# Sheet1.net
KiCad netlist of a schematic drawn in Altium Designer
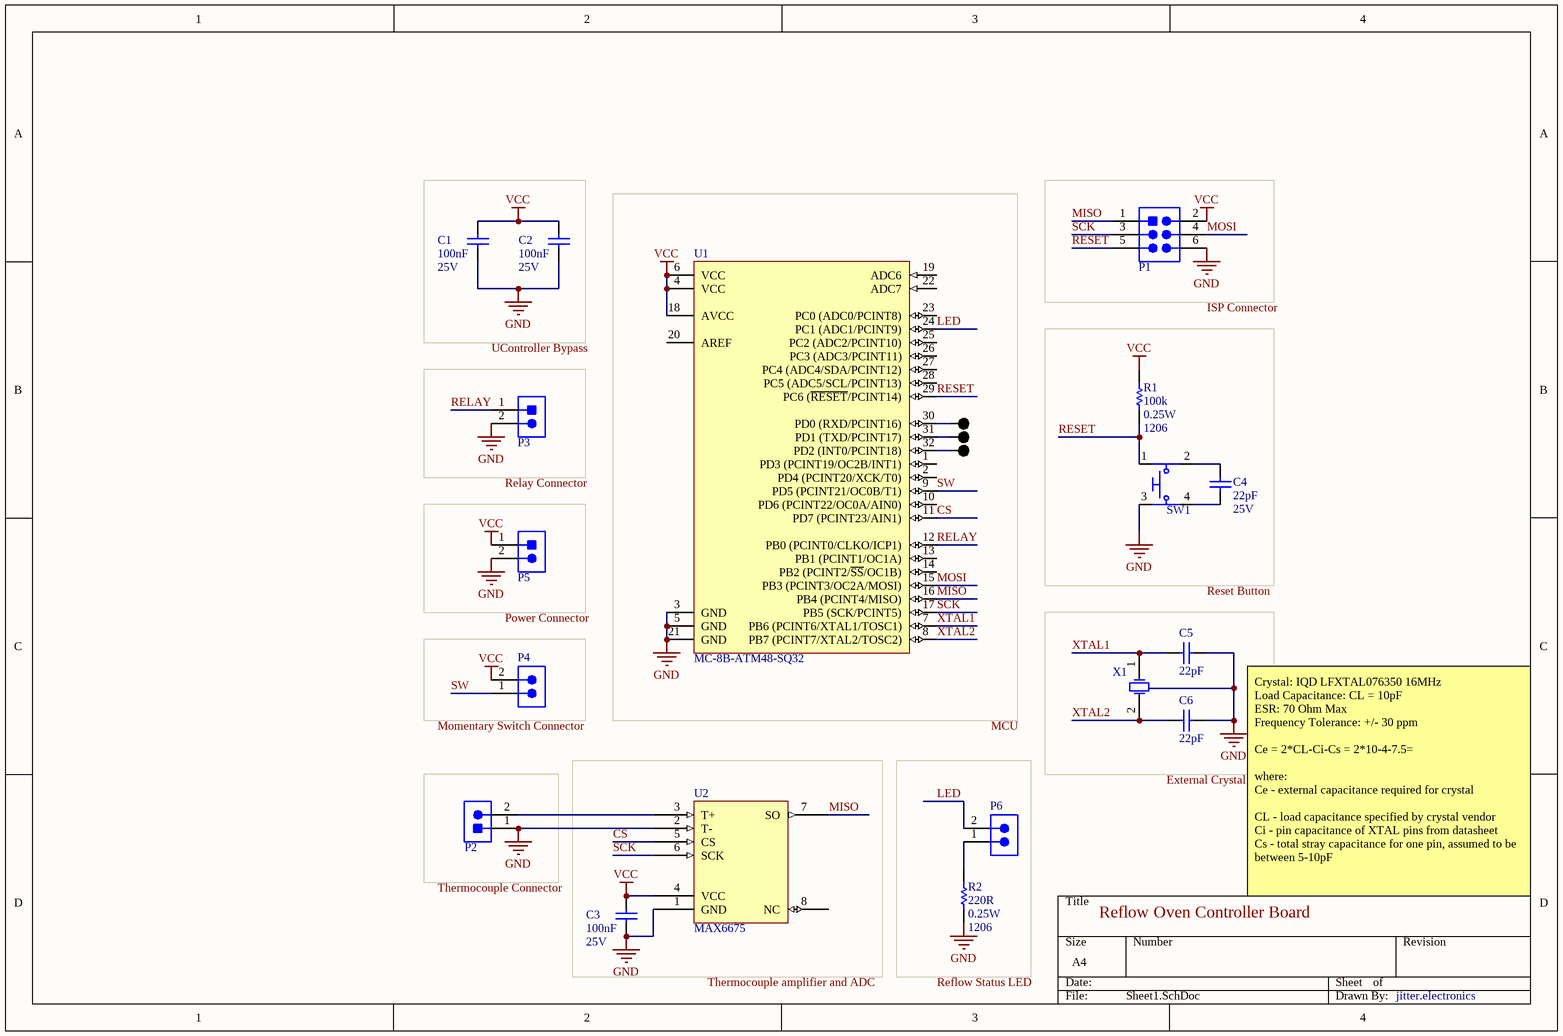
[diagram p0: Sheet1.SchDoc]

(export (version "E")
  (design (tool "Eeschema 10.0.6"))
  (components
    (comp (ref "1")
      (value "1MM_HOLE")
      (footprint "1MM_HOLE")
      (description "1mm hole and pad for breakouts")
      (libsource (lib "PCB_mechanical") (part "1MM_HOLE"))
    )
    (comp (ref "2")
      (value "1MM_HOLE")
      (footprint "1MM_HOLE")
      (description "1mm hole and pad for breakouts")
      (libsource (lib "PCB_mechanical") (part "1MM_HOLE"))
    )
    (comp (ref "3")
      (value "1MM_HOLE")
      (footprint "1MM_HOLE")
      (description "1mm hole and pad for breakouts")
      (libsource (lib "PCB_mechanical") (part "1MM_HOLE"))
    )
    (comp (ref "C1")
      (value "100nF")
      (footprint "CAPC0805(2012)75_N")
      (fields (field (name "VOLTAGE") "25V") (field (name "Comment") "CAP"))
      (libsource (lib "capacitors") (part "CAP"))
    )
    (comp (ref "C2")
      (value "100nF")
      (footprint "CAPC0805(2012)75_N")
      (fields (field (name "VOLTAGE") "25V") (field (name "Comment") "CAP"))
      (libsource (lib "capacitors") (part "CAP"))
    )
    (comp (ref "C3")
      (value "100nF")
      (footprint "CAPC0805(2012)75_N")
      (fields (field (name "VOLTAGE") "25V") (field (name "Comment") "CAP"))
      (libsource (lib "capacitors") (part "CAP"))
    )
    (comp (ref "C4")
      (value "22pF")
      (footprint "CAPC0805(2012)75_N")
      (fields (field (name "VOLTAGE") "25V") (field (name "Comment") "CAP"))
      (libsource (lib "capacitors") (part "CAP"))
    )
    (comp (ref "C5")
      (value "22pF")
      (footprint "CAPC0805(2012)75_N")
      (fields (field (name "VOLTAGE") "25V") (field (name "Comment") "CAP"))
      (libsource (lib "capacitors") (part "CAP"))
    )
    (comp (ref "C6")
      (value "22pF")
      (footprint "CAPC0805(2012)75_N")
      (fields (field (name "VOLTAGE") "25V") (field (name "Comment") "CAP"))
      (libsource (lib "capacitors") (part "CAP"))
    )
    (comp (ref "P1")
      (value "2X3-2.54mm-HEADER")
      (footprint "PCE-BH2542-10-SPGRH-3.0")
      (description "2x3 2.54mm Header")
      (libsource (lib "connectors") (part "2X3-2.54mm-HEADER"))
    )
    (comp (ref "P2")
      (value "CTBP5000/2")
      (footprint "Camden Boss CTBP5000/2")
      (description "Socket, Screw Terminal Block, 2-Leads, Pitch 5mm, 90 Degree Angle, Through-Hole")
      (libsource (lib "") (part "CTBP5000/2_1"))
    )
    (comp (ref "P3")
      (value "CTBP5000/2")
      (footprint "Camden Boss CTBP5000/2")
      (description "Socket, Screw Terminal Block, 2-Leads, Pitch 5mm, 90 Degree Angle, Through-Hole")
      (libsource (lib "connectors") (part "CTBP5000/2"))
    )
    (comp (ref "P4")
      (value "B2B-XH-A HEADER")
      (footprint "B2B-XH-A")
      (description "Wire-To-Board Connector, Vertical, 2.5 mm, 2 Contacts, Header, XH Series, Through Hole, 1 Rows")
      (libsource (lib "connectors") (part "B2B-XH-A HEADER"))
    )
    (comp (ref "P5")
      (value "CTBP5000/2")
      (footprint "Camden Boss CTBP5000/2")
      (description "Socket, Screw Terminal Block, 2-Leads, Pitch 5mm, 90 Degree Angle, Through-Hole")
      (libsource (lib "connectors") (part "CTBP5000/2"))
    )
    (comp (ref "P6")
      (value "B2B-XH-A HEADER")
      (footprint "B2B-XH-A")
      (description "Wire-To-Board Connector, Vertical, 2.5 mm, 2 Contacts, Header, XH Series, Through Hole, 1 Rows")
      (libsource (lib "connectors") (part "B2B-XH-A HEADER"))
    )
    (comp (ref "R1")
      (value "100k")
      (footprint "RESC1206(3216)_N")
      (fields (field (name "RATING") "0.25W") (field (name "FOOT") "1206") (field (name "Comment") "RES"))
      (libsource (lib "resistors") (part "RES"))
    )
    (comp (ref "R2")
      (value "220R")
      (footprint "RESC1206(3216)_N")
      (fields (field (name "RATING") "0.25W") (field (name "FOOT") "1206") (field (name "Comment") "RES"))
      (libsource (lib "resistors") (part "RES"))
    )
    (comp (ref "SW1")
      (value "SW-SPST-4_A")
      (footprint "sw_PB_SMD")
      (libsource (lib "switches") (part "SW-SPST-4_A"))
    )
    (comp (ref "U1")
      (value "MC-8B-ATM48-SQ32")
      (footprint "32A_L")
      (description "ATMEGA 328P")
      (libsource (lib "microcontrollers") (part "MC-8B-ATM48-SQ32"))
    )
    (comp (ref "U2")
      (value "MAX6675")
      (footprint "D0008A_N")
      (libsource (lib "Amplifiers") (part "MAX 6675"))
    )
    (comp (ref "X1")
      (value "LFXTAL076350")
      (footprint "LFXTAL076350")
      (description "16MHz SMD crystal")
      (libsource (lib "Crystal") (part "LFXTAL076350"))
    )
  )
  (nets
    (net (code "1") (name "/CS") (class "Default")
      (node (ref "U1") (pin "11") (pinfunction "PD7_(PCINT23/AIN1)_11") (pintype "bidirectional"))
      (node (ref "U2") (pin "5") (pinfunction "CS_5") (pintype "input"))
    )
    (net (code "2") (name "/LED") (class "Default")
      (node (ref "P6") (pin "2") (pinfunction "2_2") (pintype "passive"))
      (node (ref "U1") (pin "24") (pinfunction "PC1_(ADC1/PCINT9)_24") (pintype "bidirectional"))
    )
    (net (code "3") (name "/MISO") (class "Default")
      (node (ref "P1") (pin "1") (pinfunction "1_1") (pintype "passive"))
      (node (ref "U1") (pin "16") (pinfunction "PB4_(PCINT4/MISO)_16") (pintype "bidirectional"))
      (node (ref "U2") (pin "7") (pinfunction "SO_7") (pintype "output"))
    )
    (net (code "4") (name "/MOSI") (class "Default")
      (node (ref "P1") (pin "4") (pinfunction "4_4") (pintype "passive"))
      (node (ref "U1") (pin "15") (pinfunction "PB3_(PCINT3/OC2A/MOSI)_15") (pintype "bidirectional"))
    )
    (net (code "5") (name "/RELAY") (class "Default")
      (node (ref "P3") (pin "1") (pinfunction "1_1") (pintype "passive"))
      (node (ref "U1") (pin "12") (pinfunction "PB0_(PCINT0/CLKO/ICP1)_12") (pintype "bidirectional"))
    )
    (net (code "6") (name "/RESET") (class "Default")
      (node (ref "P1") (pin "5") (pinfunction "5_5") (pintype "passive"))
      (node (ref "R1") (pin "1") (pinfunction "1_1") (pintype "passive"))
      (node (ref "SW1") (pin "1") (pinfunction "1_1") (pintype "passive"))
      (node (ref "U1") (pin "29") (pinfunction "PC6_(~{RESET}/PCINT14)_29") (pintype "bidirectional"))
    )
    (net (code "7") (name "/SCK") (class "Default")
      (node (ref "P1") (pin "3") (pinfunction "3_3") (pintype "passive"))
      (node (ref "U1") (pin "17") (pinfunction "PB5_(SCK/PCINT5)_17") (pintype "bidirectional"))
      (node (ref "U2") (pin "6") (pinfunction "SCK_6") (pintype "input"))
    )
    (net (code "8") (name "/SW") (class "Default")
      (node (ref "P4") (pin "1") (pinfunction "1_1") (pintype "passive"))
      (node (ref "U1") (pin "9") (pinfunction "PD5_(PCINT21/OC0B/T1)_9") (pintype "bidirectional"))
    )
    (net (code "9") (name "/XTAL1") (class "Default")
      (node (ref "C5") (pin "2") (pinfunction "2_2") (pintype "passive"))
      (node (ref "U1") (pin "7") (pinfunction "PB6_(PCINT6/XTAL1/TOSC1)_7") (pintype "bidirectional"))
      (node (ref "X1") (pin "1") (pinfunction "X2_1") (pintype "passive"))
    )
    (net (code "10") (name "/XTAL2") (class "Default")
      (node (ref "C6") (pin "2") (pinfunction "2_2") (pintype "passive"))
      (node (ref "U1") (pin "8") (pinfunction "PB7_(PCINT7/XTAL2/TOSC2)_8") (pintype "bidirectional"))
      (node (ref "X1") (pin "2") (pinfunction "X1_2") (pintype "passive"))
    )
    (net (code "11") (name "GND") (class "Default")
      (node (ref "C1") (pin "1") (pinfunction "1_1") (pintype "passive"))
      (node (ref "C2") (pin "1") (pinfunction "1_1") (pintype "passive"))
      (node (ref "C3") (pin "1") (pinfunction "1_1") (pintype "passive"))
      (node (ref "C5") (pin "1") (pinfunction "1_1") (pintype "passive"))
      (node (ref "C6") (pin "1") (pinfunction "1_1") (pintype "passive"))
      (node (ref "P1") (pin "6") (pinfunction "6_6") (pintype "passive"))
      (node (ref "P2") (pin "1") (pinfunction "1_1") (pintype "passive"))
      (node (ref "P3") (pin "2") (pinfunction "2_2") (pintype "passive"))
      (node (ref "P5") (pin "2") (pinfunction "2_2") (pintype "passive"))
      (node (ref "R2") (pin "2") (pinfunction "2_2") (pintype "passive"))
      (node (ref "SW1") (pin "3") (pinfunction "3_3") (pintype "passive"))
      (node (ref "U1") (pin "21") (pinfunction "GND_21") (pintype "power_in"))
      (node (ref "U1") (pin "3") (pinfunction "GND_3") (pintype "power_in"))
      (node (ref "U1") (pin "5") (pinfunction "GND_5") (pintype "power_in"))
      (node (ref "U2") (pin "1") (pinfunction "GND_1") (pintype "power_in"))
      (node (ref "U2") (pin "2") (pinfunction "T-_2") (pintype "input"))
      (node (ref "X1") (pin "3") (pinfunction "GND_3") (pintype "power_in"))
    )
    (net (code "12") (name "Net-(C4-Pad1)") (class "Default")
      (node (ref "C4") (pin "1") (pinfunction "1_1") (pintype "passive"))
      (node (ref "SW1") (pin "2") (pinfunction "2_2") (pintype "passive"))
    )
    (net (code "13") (name "Net-(C4-Pad2)") (class "Default")
      (node (ref "C4") (pin "2") (pinfunction "2_2") (pintype "passive"))
      (node (ref "SW1") (pin "4") (pinfunction "4_4") (pintype "passive"))
    )
    (net (code "14") (name "Net-(P6-Pad1)") (class "Default")
      (node (ref "P6") (pin "1") (pinfunction "1_1") (pintype "passive"))
      (node (ref "R2") (pin "1") (pinfunction "1_1") (pintype "passive"))
    )
    (net (code "15") (name "Net-(U1-PD0_(RXD{slash}PCINT16))") (class "Default")
      (node (ref "1") (pin "1") (pinfunction "1_1") (pintype "passive"))
      (node (ref "U1") (pin "30") (pinfunction "PD0_(RXD/PCINT16)_30") (pintype "bidirectional"))
    )
    (net (code "16") (name "Net-(U1-PD1_(TXD{slash}PCINT17))") (class "Default")
      (node (ref "2") (pin "1") (pinfunction "1_1") (pintype "passive"))
      (node (ref "U1") (pin "31") (pinfunction "PD1_(TXD/PCINT17)_31") (pintype "bidirectional"))
    )
    (net (code "17") (name "Net-(U1-PD2_(INT0{slash}PCINT18))") (class "Default")
      (node (ref "3") (pin "1") (pinfunction "1_1") (pintype "passive"))
      (node (ref "U1") (pin "32") (pinfunction "PD2_(INT0/PCINT18)_32") (pintype "bidirectional"))
    )
    (net (code "18") (name "Net-(U2-T+)") (class "Default")
      (node (ref "P2") (pin "2") (pinfunction "2_2") (pintype "passive"))
      (node (ref "U2") (pin "3") (pinfunction "T+_3") (pintype "input"))
    )
    (net (code "19") (name "VCC") (class "Default")
      (node (ref "C1") (pin "2") (pinfunction "2_2") (pintype "passive"))
      (node (ref "C2") (pin "2") (pinfunction "2_2") (pintype "passive"))
      (node (ref "C3") (pin "2") (pinfunction "2_2") (pintype "passive"))
      (node (ref "P1") (pin "2") (pinfunction "2_2") (pintype "passive"))
      (node (ref "P4") (pin "2") (pinfunction "2_2") (pintype "passive"))
      (node (ref "P5") (pin "1") (pinfunction "1_1") (pintype "passive"))
      (node (ref "R1") (pin "2") (pinfunction "2_2") (pintype "passive"))
      (node (ref "U1") (pin "18") (pinfunction "AVCC_18") (pintype "power_in"))
      (node (ref "U1") (pin "4") (pinfunction "VCC_4") (pintype "power_in"))
      (node (ref "U1") (pin "6") (pinfunction "VCC_6") (pintype "power_in"))
      (node (ref "U2") (pin "4") (pinfunction "VCC_4") (pintype "power_in"))
    )
    (net (code "20") (name "unconnected-(U1-ADC6-Pad19)") (class "Default")
      (node (ref "U1") (pin "19") (pinfunction "ADC6_19") (pintype "input"))
    )
    (net (code "21") (name "unconnected-(U1-ADC7-Pad22)") (class "Default")
      (node (ref "U1") (pin "22") (pinfunction "ADC7_22") (pintype "input"))
    )
    (net (code "22") (name "unconnected-(U1-AREF-Pad20)") (class "Default")
      (node (ref "U1") (pin "20") (pinfunction "AREF_20") (pintype "passive"))
    )
    (net (code "23") (name "unconnected-(U1-PB1_(PCINT1{slash}OC1A)-Pad13)") (class "Default")
      (node (ref "U1") (pin "13") (pinfunction "PB1_(PCINT1/OC1A)_13") (pintype "bidirectional"))
    )
    (net (code "24") (name "unconnected-(U1-PB2_(PCINT2{slash}~{SS}{slash}OC1B)-Pad14)") (class "Default")
      (node (ref "U1") (pin "14") (pinfunction "PB2_(PCINT2/~{SS}/OC1B)_14") (pintype "bidirectional"))
    )
    (net (code "25") (name "unconnected-(U1-PC0_(ADC0{slash}PCINT8)-Pad23)") (class "Default")
      (node (ref "U1") (pin "23") (pinfunction "PC0_(ADC0/PCINT8)_23") (pintype "bidirectional"))
    )
    (net (code "26") (name "unconnected-(U1-PC2_(ADC2{slash}PCINT10)-Pad25)") (class "Default")
      (node (ref "U1") (pin "25") (pinfunction "PC2_(ADC2/PCINT10)_25") (pintype "bidirectional"))
    )
    (net (code "27") (name "unconnected-(U1-PC3_(ADC3{slash}PCINT11)-Pad26)") (class "Default")
      (node (ref "U1") (pin "26") (pinfunction "PC3_(ADC3/PCINT11)_26") (pintype "bidirectional"))
    )
    (net (code "28") (name "unconnected-(U1-PC4_(ADC4{slash}SDA{slash}PCINT12)-Pad27)") (class "Default")
      (node (ref "U1") (pin "27") (pinfunction "PC4_(ADC4/SDA/PCINT12)_27") (pintype "bidirectional"))
    )
    (net (code "29") (name "unconnected-(U1-PC5_(ADC5{slash}SCL{slash}PCINT13)-Pad28)") (class "Default")
      (node (ref "U1") (pin "28") (pinfunction "PC5_(ADC5/SCL/PCINT13)_28") (pintype "bidirectional"))
    )
    (net (code "30") (name "unconnected-(U1-PD3_(PCINT19{slash}OC2B{slash}INT1)-Pad1)") (class "Default")
      (node (ref "U1") (pin "1") (pinfunction "PD3_(PCINT19/OC2B/INT1)_1") (pintype "bidirectional"))
    )
    (net (code "31") (name "unconnected-(U1-PD4_(PCINT20{slash}XCK{slash}T0)-Pad2)") (class "Default")
      (node (ref "U1") (pin "2") (pinfunction "PD4_(PCINT20/XCK/T0)_2") (pintype "bidirectional"))
    )
    (net (code "32") (name "unconnected-(U1-PD6_(PCINT22{slash}OC0A{slash}AIN0)-Pad10)") (class "Default")
      (node (ref "U1") (pin "10") (pinfunction "PD6_(PCINT22/OC0A/AIN0)_10") (pintype "bidirectional"))
    )
    (net (code "33") (name "unconnected-(U2-NC-Pad8)") (class "Default")
      (node (ref "U2") (pin "8") (pinfunction "NC_8") (pintype "bidirectional"))
    )
  )
)
